# 02_PMIC_PMU.net
KiCad netlist of a schematic drawn in Altium Designer
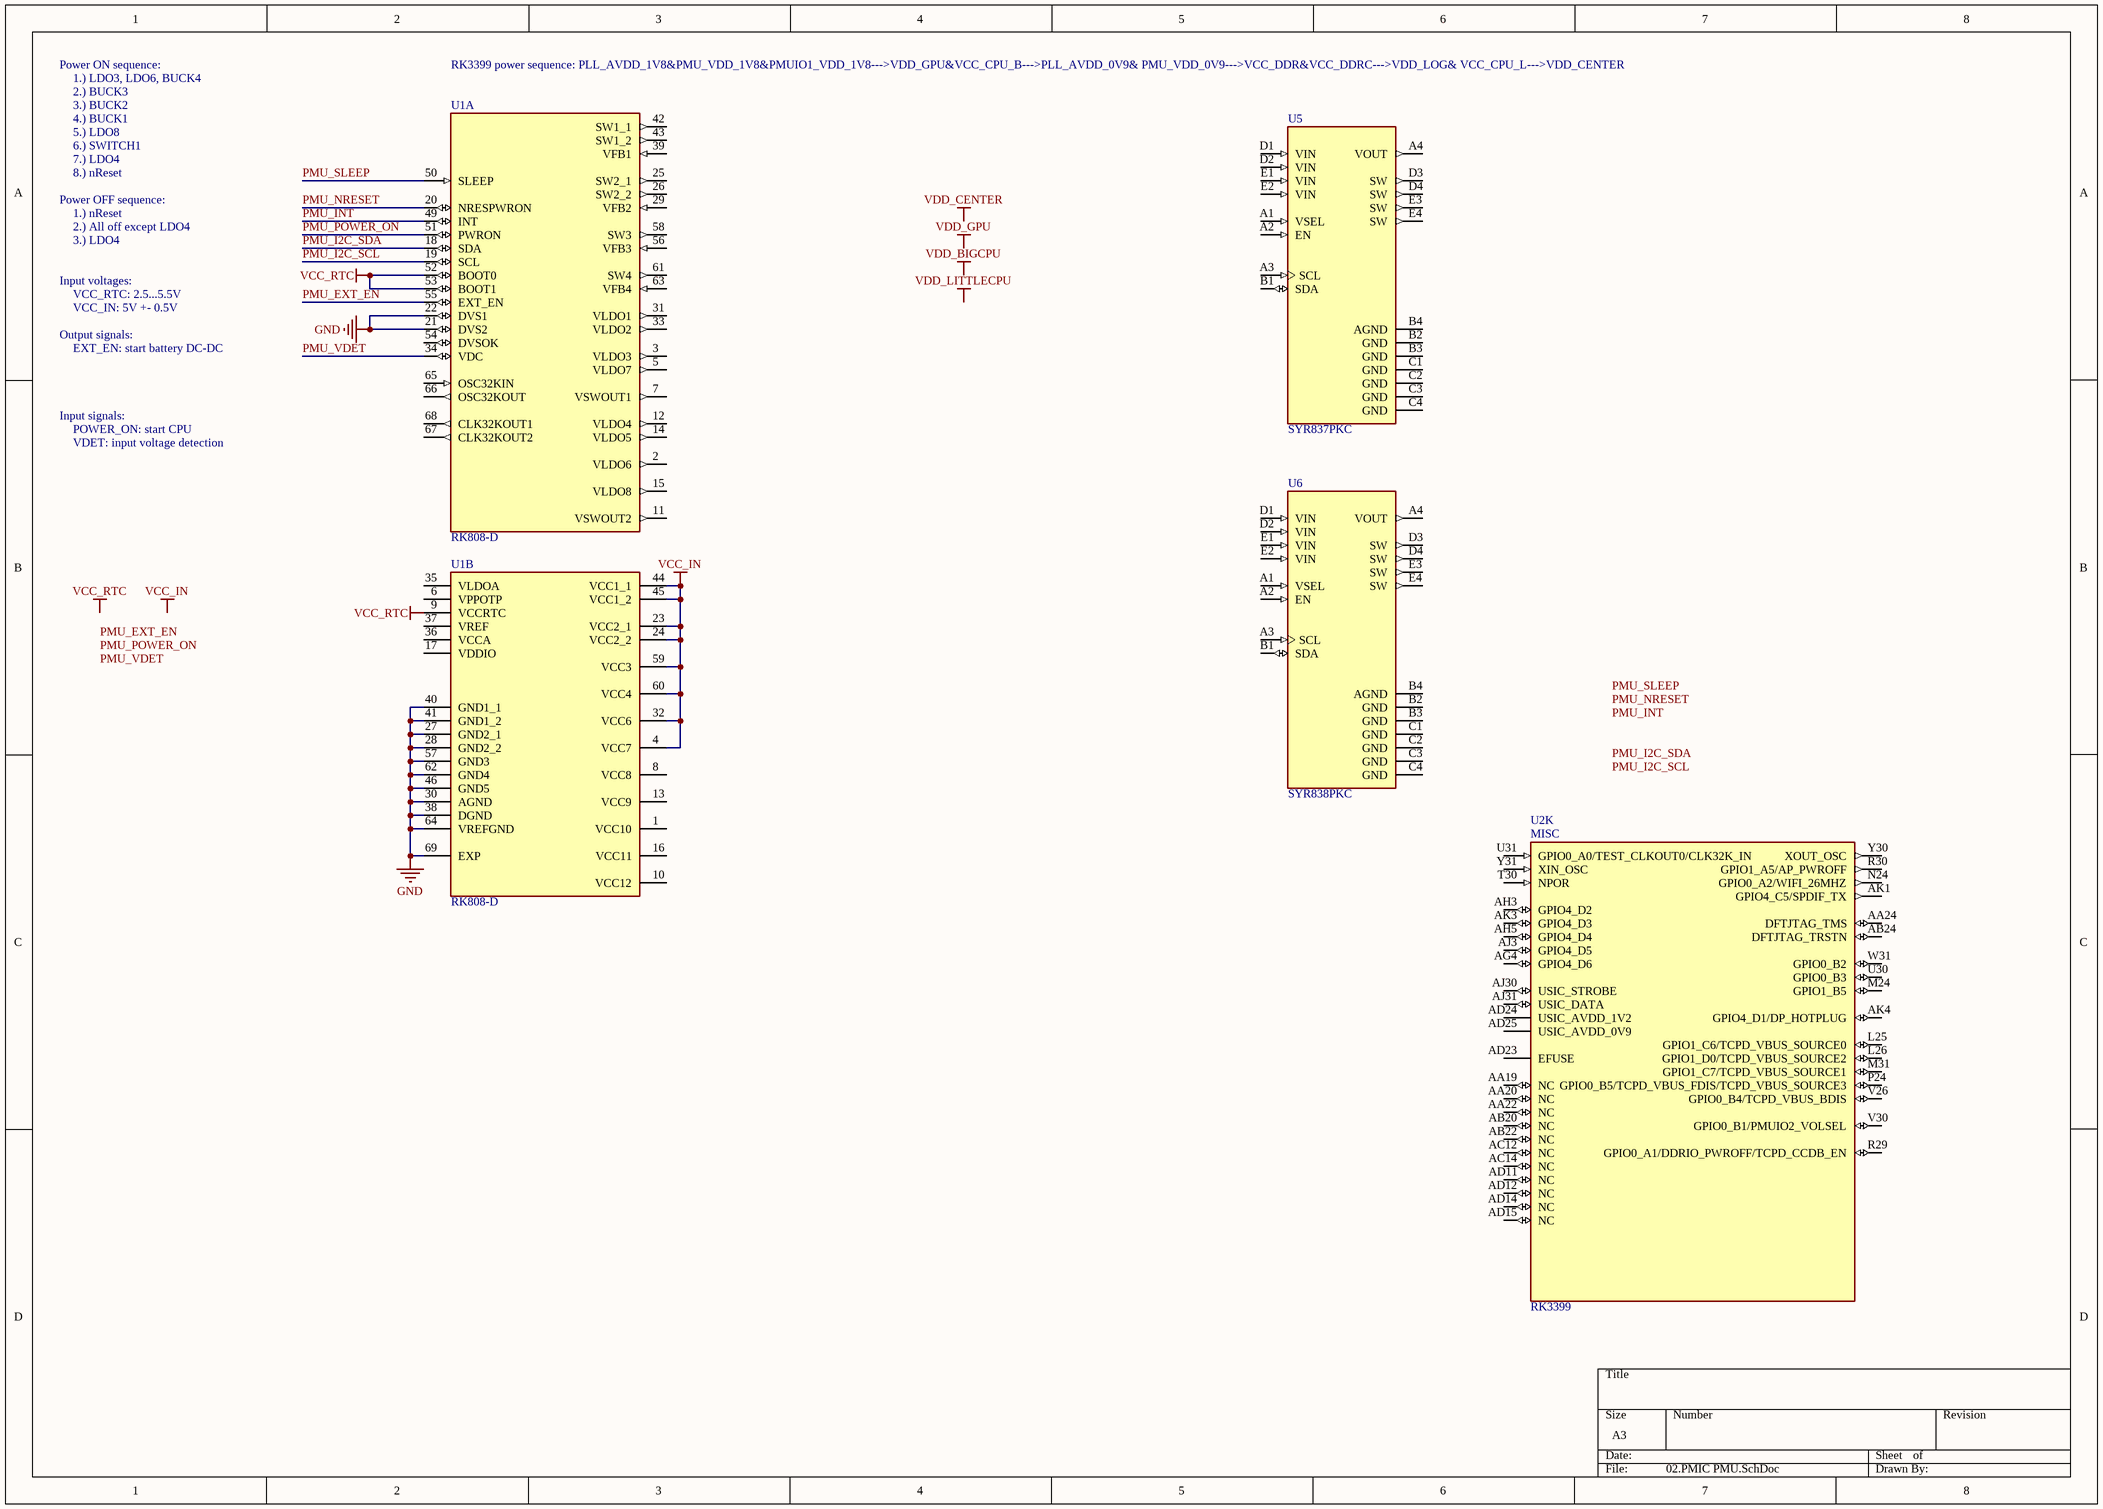
[diagram p0: 02.PMIC PMU.SchDoc]

(export (version "E")
  (design (tool "Eeschema 10.0.6"))
  (components
    (comp (ref "U1")
      (value "RK808-D")
      (footprint "QFN35P700X700X80-69N")
      (description "Power Management System")
      (fields (field (name "MF") "Fuzhou Rockchip Electronics Co"))
      (libsource (lib "RK808-D") (part "RK808-D"))
    )
    (comp (ref "U2")
      (value "RK3399")
      (footprint "BGA828C65P31X31_2100X2100X161N")
      (description "RK3399 ROCK Pi 4 Model A 2GB - ARMÂ® CortexÂ®-A53, CortexÂ®-A72 MPU Embedded Evaluation Board")
      (fields (field (name "MF") "Rockchip"))
      (libsource (lib "RK3399") (part "RK3399"))
    )
    (comp (ref "U5")
      (value "SYR837PKC")
      (footprint "BGA20N40P5X4_196X156X66N")
      (fields (field (name "MF") "Silergy"))
      (libsource (lib "SYR837PKC") (part "SYR837PKC"))
    )
    (comp (ref "U6")
      (value "SYR838PKC")
      (footprint "BGA20N40P5X4_196X156X66N")
      (fields (field (name "MF") "Silergy") (field (name "MP") "SYR837PKC"))
      (libsource (lib "SYR837PKC") (part "SYR837PKC"))
    )
  )
  (nets
    (net (code "1") (name "/PMU_EXT_EN") (class "Default")
      (node (ref "U1") (pin "55") (pinfunction "EXT_EN_55") (pintype "bidirectional"))
    )
    (net (code "2") (name "/PMU_I2C_SCL") (class "Default")
      (node (ref "U1") (pin "19") (pinfunction "SCL_19") (pintype "bidirectional"))
    )
    (net (code "3") (name "/PMU_I2C_SDA") (class "Default")
      (node (ref "U1") (pin "18") (pinfunction "SDA_18") (pintype "bidirectional"))
    )
    (net (code "4") (name "/PMU_INT") (class "Default")
      (node (ref "U1") (pin "49") (pinfunction "INT_49") (pintype "bidirectional"))
    )
    (net (code "5") (name "/PMU_NRESET") (class "Default")
      (node (ref "U1") (pin "20") (pinfunction "NRESPWRON_20") (pintype "bidirectional"))
    )
    (net (code "6") (name "/PMU_POWER_ON") (class "Default")
      (node (ref "U1") (pin "51") (pinfunction "PWRON_51") (pintype "bidirectional"))
    )
    (net (code "7") (name "/PMU_SLEEP") (class "Default")
      (node (ref "U1") (pin "50") (pinfunction "SLEEP_50") (pintype "input"))
    )
    (net (code "8") (name "/PMU_VDET") (class "Default")
      (node (ref "U1") (pin "34") (pinfunction "VDC_34") (pintype "bidirectional"))
    )
    (net (code "9") (name "GND") (class "Default")
      (node (ref "U1") (pin "21") (pinfunction "DVS2_21") (pintype "bidirectional"))
      (node (ref "U1") (pin "22") (pinfunction "DVS1_22") (pintype "bidirectional"))
      (node (ref "U1") (pin "27") (pinfunction "GND2_1_27") (pintype "power_in"))
      (node (ref "U1") (pin "28") (pinfunction "GND2_2_28") (pintype "power_in"))
      (node (ref "U1") (pin "30") (pinfunction "AGND_30") (pintype "power_in"))
      (node (ref "U1") (pin "38") (pinfunction "DGND_38") (pintype "power_in"))
      (node (ref "U1") (pin "40") (pinfunction "GND1_1_40") (pintype "power_in"))
      (node (ref "U1") (pin "41") (pinfunction "GND1_2_41") (pintype "power_in"))
      (node (ref "U1") (pin "46") (pinfunction "GND5_46") (pintype "power_in"))
      (node (ref "U1") (pin "57") (pinfunction "GND3_57") (pintype "power_in"))
      (node (ref "U1") (pin "62") (pinfunction "GND4_62") (pintype "power_in"))
      (node (ref "U1") (pin "64") (pinfunction "VREFGND_64") (pintype "power_in"))
      (node (ref "U1") (pin "69") (pinfunction "EXP_69") (pintype "power_in"))
    )
    (net (code "10") (name "VCC_IN") (class "Default")
      (node (ref "U1") (pin "23") (pinfunction "VCC2_1_23") (pintype "power_in"))
      (node (ref "U1") (pin "24") (pinfunction "VCC2_2_24") (pintype "power_in"))
      (node (ref "U1") (pin "32") (pinfunction "VCC6_32") (pintype "power_in"))
      (node (ref "U1") (pin "4") (pinfunction "VCC7_4") (pintype "power_in"))
      (node (ref "U1") (pin "44") (pinfunction "VCC1_1_44") (pintype "power_in"))
      (node (ref "U1") (pin "45") (pinfunction "VCC1_2_45") (pintype "power_in"))
      (node (ref "U1") (pin "59") (pinfunction "VCC3_59") (pintype "power_in"))
      (node (ref "U1") (pin "60") (pinfunction "VCC4_60") (pintype "power_in"))
    )
    (net (code "11") (name "VCC_RTC") (class "Default")
      (node (ref "U1") (pin "52") (pinfunction "BOOT0_52") (pintype "bidirectional"))
      (node (ref "U1") (pin "53") (pinfunction "BOOT1_53") (pintype "bidirectional"))
      (node (ref "U1") (pin "9") (pinfunction "VCCRTC_9") (pintype "power_in"))
    )
    (net (code "16") (name "unconnected-(U1A-CLK32KOUT1-Pad68)") (class "Default")
      (node (ref "U1") (pin "68") (pinfunction "CLK32KOUT1_68") (pintype "output"))
    )
    (net (code "17") (name "unconnected-(U1A-CLK32KOUT2-Pad67)") (class "Default")
      (node (ref "U1") (pin "67") (pinfunction "CLK32KOUT2_67") (pintype "output"))
    )
    (net (code "18") (name "unconnected-(U1A-DVSOK-Pad54)") (class "Default")
      (node (ref "U1") (pin "54") (pinfunction "DVSOK_54") (pintype "bidirectional"))
    )
    (net (code "19") (name "unconnected-(U1A-OSC32KIN-Pad65)") (class "Default")
      (node (ref "U1") (pin "65") (pinfunction "OSC32KIN_65") (pintype "input"))
    )
    (net (code "20") (name "unconnected-(U1A-OSC32KOUT-Pad66)") (class "Default")
      (node (ref "U1") (pin "66") (pinfunction "OSC32KOUT_66") (pintype "output"))
    )
    (net (code "21") (name "unconnected-(U1A-SW1_1-Pad42)") (class "Default")
      (node (ref "U1") (pin "42") (pinfunction "SW1_1_42") (pintype "output"))
    )
    (net (code "22") (name "unconnected-(U1A-SW1_2-Pad43)") (class "Default")
      (node (ref "U1") (pin "43") (pinfunction "SW1_2_43") (pintype "output"))
    )
    (net (code "23") (name "unconnected-(U1A-SW2_1-Pad25)") (class "Default")
      (node (ref "U1") (pin "25") (pinfunction "SW2_1_25") (pintype "output"))
    )
    (net (code "24") (name "unconnected-(U1A-SW2_2-Pad26)") (class "Default")
      (node (ref "U1") (pin "26") (pinfunction "SW2_2_26") (pintype "output"))
    )
    (net (code "25") (name "unconnected-(U1A-SW3-Pad58)") (class "Default")
      (node (ref "U1") (pin "58") (pinfunction "SW3_58") (pintype "output"))
    )
    (net (code "26") (name "unconnected-(U1A-SW4-Pad61)") (class "Default")
      (node (ref "U1") (pin "61") (pinfunction "SW4_61") (pintype "output"))
    )
    (net (code "27") (name "unconnected-(U1A-VFB1-Pad39)") (class "Default")
      (node (ref "U1") (pin "39") (pinfunction "VFB1_39") (pintype "input"))
    )
    (net (code "28") (name "unconnected-(U1A-VFB2-Pad29)") (class "Default")
      (node (ref "U1") (pin "29") (pinfunction "VFB2_29") (pintype "input"))
    )
    (net (code "29") (name "unconnected-(U1A-VFB3-Pad56)") (class "Default")
      (node (ref "U1") (pin "56") (pinfunction "VFB3_56") (pintype "input"))
    )
    (net (code "30") (name "unconnected-(U1A-VFB4-Pad63)") (class "Default")
      (node (ref "U1") (pin "63") (pinfunction "VFB4_63") (pintype "input"))
    )
    (net (code "31") (name "unconnected-(U1A-VLDO1-Pad31)") (class "Default")
      (node (ref "U1") (pin "31") (pinfunction "VLDO1_31") (pintype "output"))
    )
    (net (code "32") (name "unconnected-(U1A-VLDO2-Pad33)") (class "Default")
      (node (ref "U1") (pin "33") (pinfunction "VLDO2_33") (pintype "output"))
    )
    (net (code "33") (name "unconnected-(U1A-VLDO3-Pad3)") (class "Default")
      (node (ref "U1") (pin "3") (pinfunction "VLDO3_3") (pintype "output"))
    )
    (net (code "34") (name "unconnected-(U1A-VLDO4-Pad12)") (class "Default")
      (node (ref "U1") (pin "12") (pinfunction "VLDO4_12") (pintype "output"))
    )
    (net (code "35") (name "unconnected-(U1A-VLDO5-Pad14)") (class "Default")
      (node (ref "U1") (pin "14") (pinfunction "VLDO5_14") (pintype "output"))
    )
    (net (code "36") (name "unconnected-(U1A-VLDO6-Pad2)") (class "Default")
      (node (ref "U1") (pin "2") (pinfunction "VLDO6_2") (pintype "output"))
    )
    (net (code "37") (name "unconnected-(U1A-VLDO7-Pad5)") (class "Default")
      (node (ref "U1") (pin "5") (pinfunction "VLDO7_5") (pintype "output"))
    )
    (net (code "38") (name "unconnected-(U1A-VLDO8-Pad15)") (class "Default")
      (node (ref "U1") (pin "15") (pinfunction "VLDO8_15") (pintype "output"))
    )
    (net (code "39") (name "unconnected-(U1A-VSWOUT1-Pad7)") (class "Default")
      (node (ref "U1") (pin "7") (pinfunction "VSWOUT1_7") (pintype "output"))
    )
    (net (code "40") (name "unconnected-(U1A-VSWOUT2-Pad11)") (class "Default")
      (node (ref "U1") (pin "11") (pinfunction "VSWOUT2_11") (pintype "output"))
    )
    (net (code "41") (name "unconnected-(U1B-VCC8-Pad8)") (class "Default")
      (node (ref "U1") (pin "8") (pinfunction "VCC8_8") (pintype "power_in"))
    )
    (net (code "42") (name "unconnected-(U1B-VCC9-Pad13)") (class "Default")
      (node (ref "U1") (pin "13") (pinfunction "VCC9_13") (pintype "power_in"))
    )
    (net (code "43") (name "unconnected-(U1B-VCC10-Pad1)") (class "Default")
      (node (ref "U1") (pin "1") (pinfunction "VCC10_1") (pintype "power_in"))
    )
    (net (code "44") (name "unconnected-(U1B-VCC11-Pad16)") (class "Default")
      (node (ref "U1") (pin "16") (pinfunction "VCC11_16") (pintype "power_in"))
    )
    (net (code "45") (name "unconnected-(U1B-VCC12-Pad10)") (class "Default")
      (node (ref "U1") (pin "10") (pinfunction "VCC12_10") (pintype "power_in"))
    )
    (net (code "46") (name "unconnected-(U1B-VCCA-Pad36)") (class "Default")
      (node (ref "U1") (pin "36") (pinfunction "VCCA_36") (pintype "power_in"))
    )
    (net (code "47") (name "unconnected-(U1B-VDDIO-Pad17)") (class "Default")
      (node (ref "U1") (pin "17") (pinfunction "VDDIO_17") (pintype "power_in"))
    )
    (net (code "48") (name "unconnected-(U1B-VLDOA-Pad35)") (class "Default")
      (node (ref "U1") (pin "35") (pinfunction "VLDOA_35") (pintype "power_in"))
    )
    (net (code "49") (name "unconnected-(U1B-VPPOTP-Pad6)") (class "Default")
      (node (ref "U1") (pin "6") (pinfunction "VPPOTP_6") (pintype "power_in"))
    )
    (net (code "50") (name "unconnected-(U1B-VREF-Pad37)") (class "Default")
      (node (ref "U1") (pin "37") (pinfunction "VREF_37") (pintype "power_in"))
    )
    (net (code "51") (name "unconnected-(U2K-DFTJTAG_TMS-PadAA24)") (class "Default")
      (node (ref "U2") (pin "AA24") (pinfunction "DFTJTAG_TMS_AA24") (pintype "bidirectional"))
    )
    (net (code "52") (name "unconnected-(U2K-DFTJTAG_TRSTN-PadAB24)") (class "Default")
      (node (ref "U2") (pin "AB24") (pinfunction "DFTJTAG_TRSTN_AB24") (pintype "bidirectional"))
    )
    (net (code "53") (name "unconnected-(U2K-EFUSE-PadAD23)") (class "Default")
      (node (ref "U2") (pin "AD23") (pinfunction "EFUSE_AD23") (pintype "passive"))
    )
    (net (code "54") (name "unconnected-(U2K-GPIO0_A0{slash}TEST_CLKOUT0{slash}CLK32K_IN-PadU31)") (class "Default")
      (node (ref "U2") (pin "U31") (pinfunction "GPIO0_A0/TEST_CLKOUT0/CLK32K_IN_U31") (pintype "input"))
    )
    (net (code "55") (name "unconnected-(U2K-GPIO0_A1{slash}DDRIO_PWROFF{slash}TCPD_CCDB_EN-PadR29)") (class "Default")
      (node (ref "U2") (pin "R29") (pinfunction "GPIO0_A1/DDRIO_PWROFF/TCPD_CCDB_EN_R29") (pintype "bidirectional"))
    )
    (net (code "56") (name "unconnected-(U2K-GPIO0_A2{slash}WIFI_26MHZ-PadN24)") (class "Default")
      (node (ref "U2") (pin "N24") (pinfunction "GPIO0_A2/WIFI_26MHZ_N24") (pintype "output"))
    )
    (net (code "57") (name "unconnected-(U2K-GPIO0_B1{slash}PMUIO2_VOLSEL-PadV30)") (class "Default")
      (node (ref "U2") (pin "V30") (pinfunction "GPIO0_B1/PMUIO2_VOLSEL_V30") (pintype "bidirectional"))
    )
    (net (code "58") (name "unconnected-(U2K-GPIO0_B2-PadW31)") (class "Default")
      (node (ref "U2") (pin "W31") (pinfunction "GPIO0_B2_W31") (pintype "bidirectional"))
    )
    (net (code "59") (name "unconnected-(U2K-GPIO0_B3-PadU30)") (class "Default")
      (node (ref "U2") (pin "U30") (pinfunction "GPIO0_B3_U30") (pintype "bidirectional"))
    )
    (net (code "60") (name "unconnected-(U2K-GPIO0_B4{slash}TCPD_VBUS_BDIS-PadV26)") (class "Default")
      (node (ref "U2") (pin "V26") (pinfunction "GPIO0_B4/TCPD_VBUS_BDIS_V26") (pintype "bidirectional"))
    )
    (net (code "61") (name "unconnected-(U2K-GPIO0_B5{slash}TCPD_VBUS_FDIS{slash}TCPD_VBUS_SOURCE3-PadP24)") (class "Default")
      (node (ref "U2") (pin "P24") (pinfunction "GPIO0_B5/TCPD_VBUS_FDIS/TCPD_VBUS_SOURCE3_P24") (pintype "bidirectional"))
    )
    (net (code "62") (name "unconnected-(U2K-GPIO1_A5{slash}AP_PWROFF-PadR30)") (class "Default")
      (node (ref "U2") (pin "R30") (pinfunction "GPIO1_A5/AP_PWROFF_R30") (pintype "output"))
    )
    (net (code "63") (name "unconnected-(U2K-GPIO1_B5-PadM24)") (class "Default")
      (node (ref "U2") (pin "M24") (pinfunction "GPIO1_B5_M24") (pintype "bidirectional"))
    )
    (net (code "64") (name "unconnected-(U2K-GPIO1_C6{slash}TCPD_VBUS_SOURCE0-PadL25)") (class "Default")
      (node (ref "U2") (pin "L25") (pinfunction "GPIO1_C6/TCPD_VBUS_SOURCE0_L25") (pintype "bidirectional"))
    )
    (net (code "65") (name "unconnected-(U2K-GPIO1_C7{slash}TCPD_VBUS_SOURCE1-PadM31)") (class "Default")
      (node (ref "U2") (pin "M31") (pinfunction "GPIO1_C7/TCPD_VBUS_SOURCE1_M31") (pintype "bidirectional"))
    )
    (net (code "66") (name "unconnected-(U2K-GPIO1_D0{slash}TCPD_VBUS_SOURCE2-PadL26)") (class "Default")
      (node (ref "U2") (pin "L26") (pinfunction "GPIO1_D0/TCPD_VBUS_SOURCE2_L26") (pintype "bidirectional"))
    )
    (net (code "67") (name "unconnected-(U2K-GPIO4_C5{slash}SPDIF_TX-PadAK1)") (class "Default")
      (node (ref "U2") (pin "AK1") (pinfunction "GPIO4_C5/SPDIF_TX_AK1") (pintype "output"))
    )
    (net (code "68") (name "unconnected-(U2K-GPIO4_D1{slash}DP_HOTPLUG-PadAK4)") (class "Default")
      (node (ref "U2") (pin "AK4") (pinfunction "GPIO4_D1/DP_HOTPLUG_AK4") (pintype "bidirectional"))
    )
    (net (code "69") (name "unconnected-(U2K-GPIO4_D2-PadAH3)") (class "Default")
      (node (ref "U2") (pin "AH3") (pinfunction "GPIO4_D2_AH3") (pintype "bidirectional"))
    )
    (net (code "70") (name "unconnected-(U2K-GPIO4_D3-PadAK3)") (class "Default")
      (node (ref "U2") (pin "AK3") (pinfunction "GPIO4_D3_AK3") (pintype "bidirectional"))
    )
    (net (code "71") (name "unconnected-(U2K-GPIO4_D4-PadAH5)") (class "Default")
      (node (ref "U2") (pin "AH5") (pinfunction "GPIO4_D4_AH5") (pintype "bidirectional"))
    )
    (net (code "72") (name "unconnected-(U2K-GPIO4_D5-PadAJ3)") (class "Default")
      (node (ref "U2") (pin "AJ3") (pinfunction "GPIO4_D5_AJ3") (pintype "bidirectional"))
    )
    (net (code "73") (name "unconnected-(U2K-GPIO4_D6-PadAG4)") (class "Default")
      (node (ref "U2") (pin "AG4") (pinfunction "GPIO4_D6_AG4") (pintype "bidirectional"))
    )
    (net (code "74") (name "unconnected-(U2K-NC-PadAA19)") (class "Default")
      (node (ref "U2") (pin "AA19") (pinfunction "NC_AA19") (pintype "bidirectional"))
    )
    (net (code "75") (name "unconnected-(U2K-NC-PadAA20)") (class "Default")
      (node (ref "U2") (pin "AA20") (pinfunction "NC_AA20") (pintype "bidirectional"))
    )
    (net (code "76") (name "unconnected-(U2K-NC-PadAA22)") (class "Default")
      (node (ref "U2") (pin "AA22") (pinfunction "NC_AA22") (pintype "bidirectional"))
    )
    (net (code "77") (name "unconnected-(U2K-NC-PadAB20)") (class "Default")
      (node (ref "U2") (pin "AB20") (pinfunction "NC_AB20") (pintype "bidirectional"))
    )
    (net (code "78") (name "unconnected-(U2K-NC-PadAB22)") (class "Default")
      (node (ref "U2") (pin "AB22") (pinfunction "NC_AB22") (pintype "bidirectional"))
    )
    (net (code "79") (name "unconnected-(U2K-NC-PadAC12)") (class "Default")
      (node (ref "U2") (pin "AC12") (pinfunction "NC_AC12") (pintype "bidirectional"))
    )
    (net (code "80") (name "unconnected-(U2K-NC-PadAC14)") (class "Default")
      (node (ref "U2") (pin "AC14") (pinfunction "NC_AC14") (pintype "bidirectional"))
    )
    (net (code "81") (name "unconnected-(U2K-NC-PadAD11)") (class "Default")
      (node (ref "U2") (pin "AD11") (pinfunction "NC_AD11") (pintype "bidirectional"))
    )
    (net (code "82") (name "unconnected-(U2K-NC-PadAD12)") (class "Default")
      (node (ref "U2") (pin "AD12") (pinfunction "NC_AD12") (pintype "bidirectional"))
    )
    (net (code "83") (name "unconnected-(U2K-NC-PadAD14)") (class "Default")
      (node (ref "U2") (pin "AD14") (pinfunction "NC_AD14") (pintype "bidirectional"))
    )
    (net (code "84") (name "unconnected-(U2K-NC-PadAD15)") (class "Default")
      (node (ref "U2") (pin "AD15") (pinfunction "NC_AD15") (pintype "bidirectional"))
    )
    (net (code "85") (name "unconnected-(U2K-NPOR-PadT30)") (class "Default")
      (node (ref "U2") (pin "T30") (pinfunction "NPOR_T30") (pintype "input"))
    )
    (net (code "86") (name "unconnected-(U2K-USIC_AVDD_0V9-PadAD25)") (class "Default")
      (node (ref "U2") (pin "AD25") (pinfunction "USIC_AVDD_0V9_AD25") (pintype "power_in"))
    )
    (net (code "87") (name "unconnected-(U2K-USIC_AVDD_1V2-PadAD24)") (class "Default")
      (node (ref "U2") (pin "AD24") (pinfunction "USIC_AVDD_1V2_AD24") (pintype "power_in"))
    )
    (net (code "88") (name "unconnected-(U2K-USIC_DATA-PadAJ31)") (class "Default")
      (node (ref "U2") (pin "AJ31") (pinfunction "USIC_DATA_AJ31") (pintype "bidirectional"))
    )
    (net (code "89") (name "unconnected-(U2K-USIC_STROBE-PadAJ30)") (class "Default")
      (node (ref "U2") (pin "AJ30") (pinfunction "USIC_STROBE_AJ30") (pintype "bidirectional"))
    )
    (net (code "90") (name "unconnected-(U2K-XIN_OSC-PadY31)") (class "Default")
      (node (ref "U2") (pin "Y31") (pinfunction "XIN_OSC_Y31") (pintype "input"))
    )
    (net (code "91") (name "unconnected-(U2K-XOUT_OSC-PadY30)") (class "Default")
      (node (ref "U2") (pin "Y30") (pinfunction "XOUT_OSC_Y30") (pintype "output"))
    )
    (net (code "92") (name "unconnected-(U5-AGND-PadB4)") (class "Default")
      (node (ref "U5") (pin "B4") (pinfunction "AGND_B4") (pintype "power_in"))
    )
    (net (code "93") (name "unconnected-(U5-EN-PadA2)") (class "Default")
      (node (ref "U5") (pin "A2") (pinfunction "EN_A2") (pintype "input"))
    )
    (net (code "94") (name "unconnected-(U5-GND-PadB2)") (class "Default")
      (node (ref "U5") (pin "B2") (pinfunction "GND_B2") (pintype "power_in"))
    )
    (net (code "95") (name "unconnected-(U5-GND-PadB3)") (class "Default")
      (node (ref "U5") (pin "B3") (pinfunction "GND_B3") (pintype "power_in"))
    )
    (net (code "96") (name "unconnected-(U5-GND-PadC1)") (class "Default")
      (node (ref "U5") (pin "C1") (pinfunction "GND_C1") (pintype "power_in"))
    )
    (net (code "97") (name "unconnected-(U5-GND-PadC2)") (class "Default")
      (node (ref "U5") (pin "C2") (pinfunction "GND_C2") (pintype "power_in"))
    )
    (net (code "98") (name "unconnected-(U5-GND-PadC3)") (class "Default")
      (node (ref "U5") (pin "C3") (pinfunction "GND_C3") (pintype "power_in"))
    )
    (net (code "99") (name "unconnected-(U5-GND-PadC4)") (class "Default")
      (node (ref "U5") (pin "C4") (pinfunction "GND_C4") (pintype "power_in"))
    )
    (net (code "100") (name "unconnected-(U5-SCL-PadA3)") (class "Default")
      (node (ref "U5") (pin "A3") (pinfunction "SCL_A3") (pintype "input"))
    )
    (net (code "101") (name "unconnected-(U5-SDA-PadB1)") (class "Default")
      (node (ref "U5") (pin "B1") (pinfunction "SDA_B1") (pintype "bidirectional"))
    )
    (net (code "102") (name "unconnected-(U5-SW-PadD3)") (class "Default")
      (node (ref "U5") (pin "D3") (pinfunction "SW_D3") (pintype "output"))
    )
    (net (code "103") (name "unconnected-(U5-SW-PadD4)") (class "Default")
      (node (ref "U5") (pin "D4") (pinfunction "SW_D4") (pintype "output"))
    )
    (net (code "104") (name "unconnected-(U5-SW-PadE3)") (class "Default")
      (node (ref "U5") (pin "E3") (pinfunction "SW_E3") (pintype "output"))
    )
    (net (code "105") (name "unconnected-(U5-SW-PadE4)") (class "Default")
      (node (ref "U5") (pin "E4") (pinfunction "SW_E4") (pintype "output"))
    )
    (net (code "106") (name "unconnected-(U5-VIN-PadD1)") (class "Default")
      (node (ref "U5") (pin "D1") (pinfunction "VIN_D1") (pintype "input"))
    )
    (net (code "107") (name "unconnected-(U5-VIN-PadD2)") (class "Default")
      (node (ref "U5") (pin "D2") (pinfunction "VIN_D2") (pintype "input"))
    )
    (net (code "108") (name "unconnected-(U5-VIN-PadE1)") (class "Default")
      (node (ref "U5") (pin "E1") (pinfunction "VIN_E1") (pintype "input"))
    )
    (net (code "109") (name "unconnected-(U5-VIN-PadE2)") (class "Default")
      (node (ref "U5") (pin "E2") (pinfunction "VIN_E2") (pintype "input"))
    )
    (net (code "110") (name "unconnected-(U5-VOUT-PadA4)") (class "Default")
      (node (ref "U5") (pin "A4") (pinfunction "VOUT_A4") (pintype "output"))
    )
    (net (code "111") (name "unconnected-(U5-VSEL-PadA1)") (class "Default")
      (node (ref "U5") (pin "A1") (pinfunction "VSEL_A1") (pintype "input"))
    )
    (net (code "112") (name "unconnected-(U6-AGND-PadB4)") (class "Default")
      (node (ref "U6") (pin "B4") (pinfunction "AGND_B4") (pintype "power_in"))
    )
    (net (code "113") (name "unconnected-(U6-EN-PadA2)") (class "Default")
      (node (ref "U6") (pin "A2") (pinfunction "EN_A2") (pintype "input"))
    )
    (net (code "114") (name "unconnected-(U6-GND-PadB2)") (class "Default")
      (node (ref "U6") (pin "B2") (pinfunction "GND_B2") (pintype "power_in"))
    )
    (net (code "115") (name "unconnected-(U6-GND-PadB3)") (class "Default")
      (node (ref "U6") (pin "B3") (pinfunction "GND_B3") (pintype "power_in"))
    )
    (net (code "116") (name "unconnected-(U6-GND-PadC1)") (class "Default")
      (node (ref "U6") (pin "C1") (pinfunction "GND_C1") (pintype "power_in"))
    )
    (net (code "117") (name "unconnected-(U6-GND-PadC2)") (class "Default")
      (node (ref "U6") (pin "C2") (pinfunction "GND_C2") (pintype "power_in"))
    )
    (net (code "118") (name "unconnected-(U6-GND-PadC3)") (class "Default")
      (node (ref "U6") (pin "C3") (pinfunction "GND_C3") (pintype "power_in"))
    )
    (net (code "119") (name "unconnected-(U6-GND-PadC4)") (class "Default")
      (node (ref "U6") (pin "C4") (pinfunction "GND_C4") (pintype "power_in"))
    )
    (net (code "120") (name "unconnected-(U6-SCL-PadA3)") (class "Default")
      (node (ref "U6") (pin "A3") (pinfunction "SCL_A3") (pintype "input"))
    )
    (net (code "121") (name "unconnected-(U6-SDA-PadB1)") (class "Default")
      (node (ref "U6") (pin "B1") (pinfunction "SDA_B1") (pintype "bidirectional"))
    )
    (net (code "122") (name "unconnected-(U6-SW-PadD3)") (class "Default")
      (node (ref "U6") (pin "D3") (pinfunction "SW_D3") (pintype "output"))
    )
    (net (code "123") (name "unconnected-(U6-SW-PadD4)") (class "Default")
      (node (ref "U6") (pin "D4") (pinfunction "SW_D4") (pintype "output"))
    )
    (net (code "124") (name "unconnected-(U6-SW-PadE3)") (class "Default")
      (node (ref "U6") (pin "E3") (pinfunction "SW_E3") (pintype "output"))
    )
    (net (code "125") (name "unconnected-(U6-SW-PadE4)") (class "Default")
      (node (ref "U6") (pin "E4") (pinfunction "SW_E4") (pintype "output"))
    )
    (net (code "126") (name "unconnected-(U6-VIN-PadD1)") (class "Default")
      (node (ref "U6") (pin "D1") (pinfunction "VIN_D1") (pintype "input"))
    )
    (net (code "127") (name "unconnected-(U6-VIN-PadD2)") (class "Default")
      (node (ref "U6") (pin "D2") (pinfunction "VIN_D2") (pintype "input"))
    )
    (net (code "128") (name "unconnected-(U6-VIN-PadE1)") (class "Default")
      (node (ref "U6") (pin "E1") (pinfunction "VIN_E1") (pintype "input"))
    )
    (net (code "129") (name "unconnected-(U6-VIN-PadE2)") (class "Default")
      (node (ref "U6") (pin "E2") (pinfunction "VIN_E2") (pintype "input"))
    )
    (net (code "130") (name "unconnected-(U6-VOUT-PadA4)") (class "Default")
      (node (ref "U6") (pin "A4") (pinfunction "VOUT_A4") (pintype "output"))
    )
    (net (code "131") (name "unconnected-(U6-VSEL-PadA1)") (class "Default")
      (node (ref "U6") (pin "A1") (pinfunction "VSEL_A1") (pintype "input"))
    )
  )
)
